# MicroMod-Artemis-ProcessorBoard.net
KiCad netlist of a schematic drawn in EAGLE
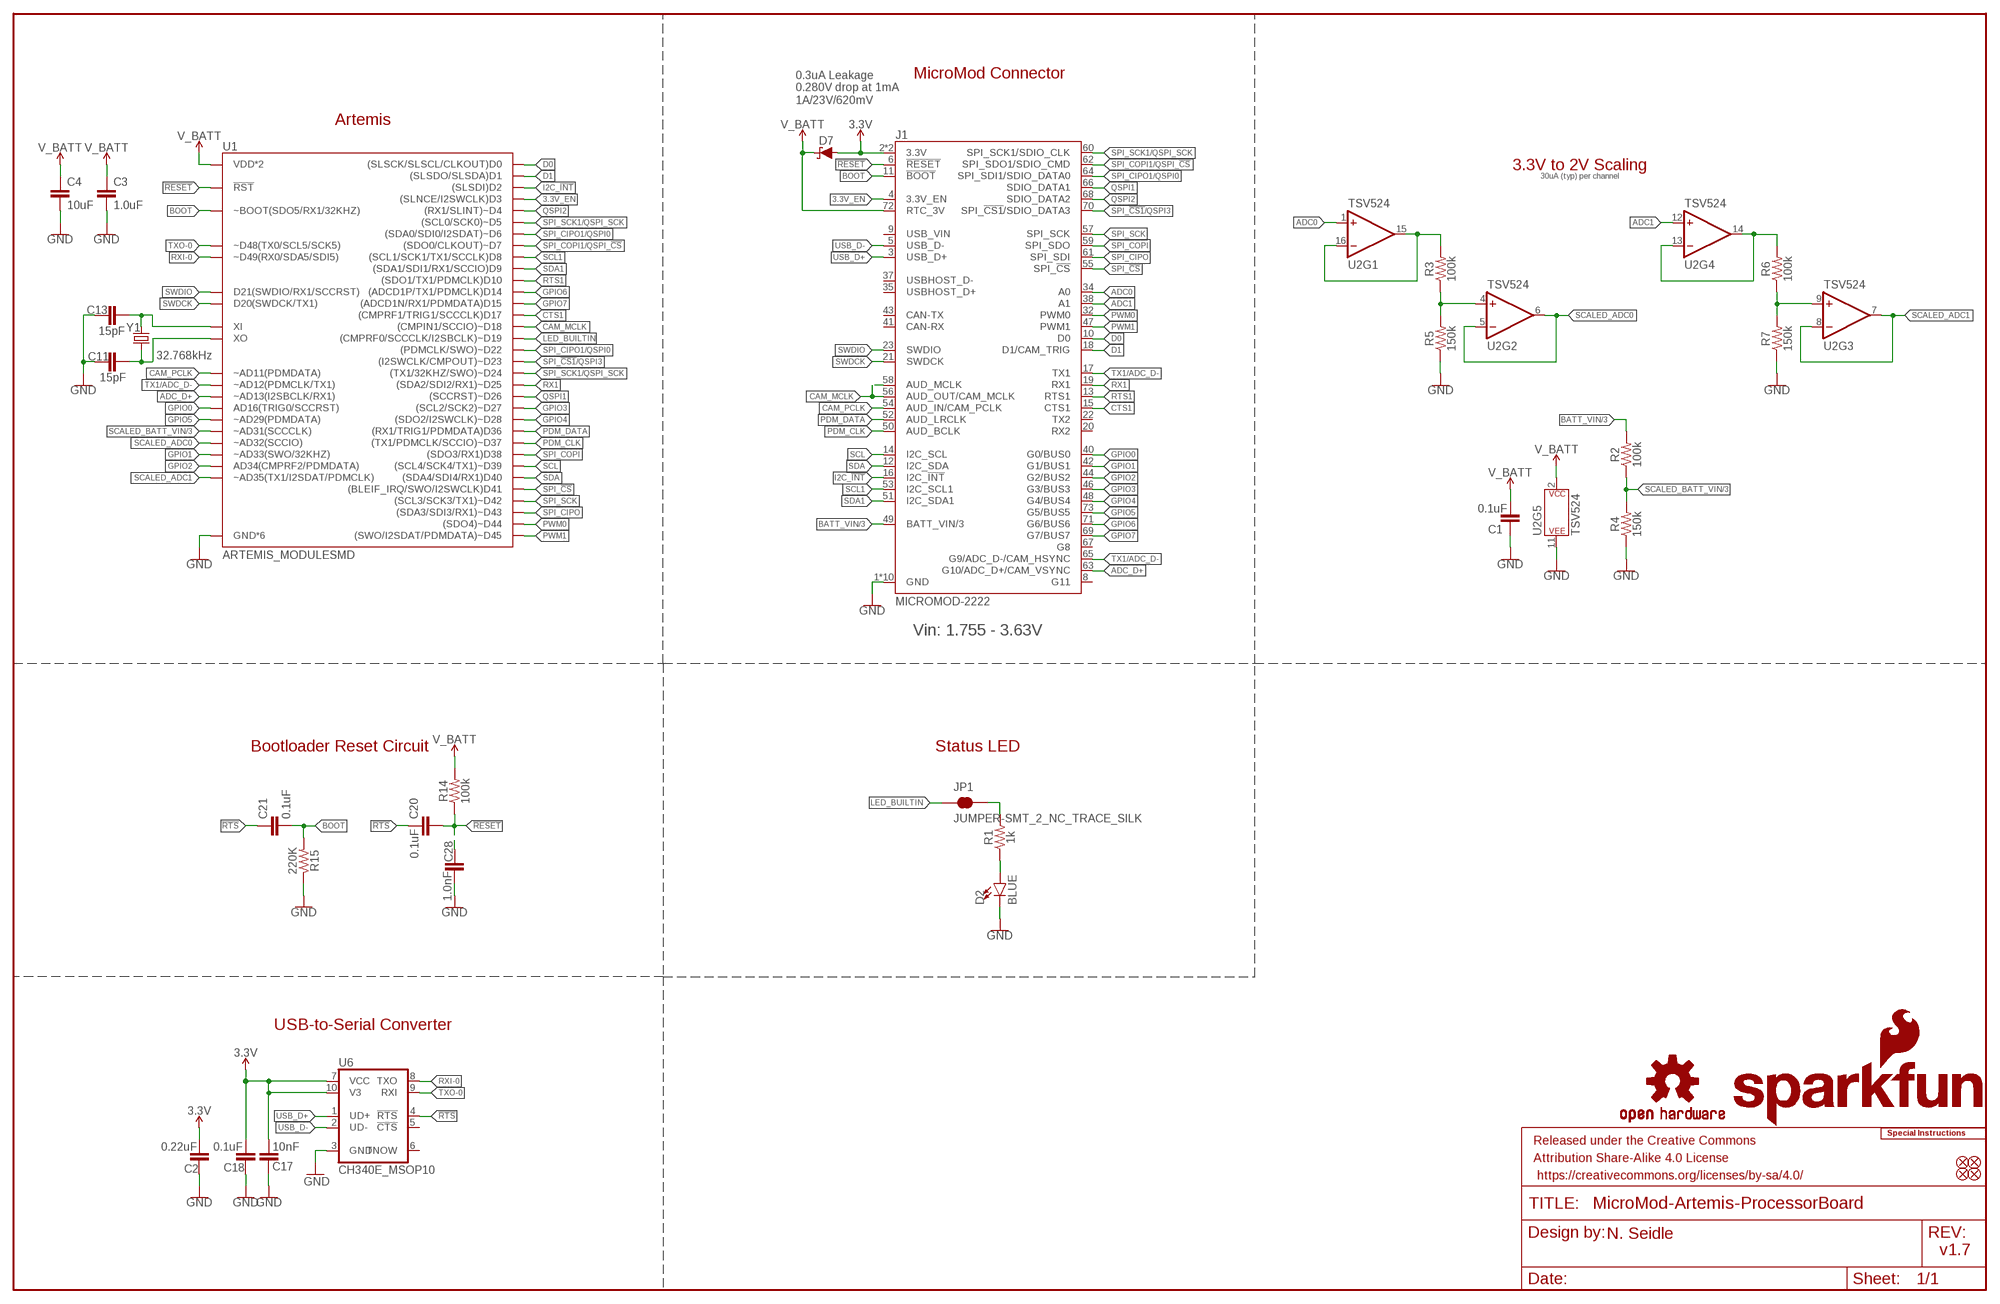
[diagram p0: schematic, sheet 1]

(export (version "E")
  (design (tool "Eeschema 10.0.6"))
  (components
    (comp (ref "C1")
      (value "0.1uF")
      (footprint "eagle-import:0402-TIGHT")
      (libsource (lib "eagle-import") (part "0.1UF-0402T-16V-10%"))
    )
    (comp (ref "C2")
      (value "0.22uF")
      (footprint "eagle-import:0402-TIGHT")
      (libsource (lib "eagle-import") (part "0.22UF-0402T-10V-10%"))
    )
    (comp (ref "C3")
      (value "1.0uF")
      (footprint "eagle-import:0402-TIGHT")
      (libsource (lib "eagle-import") (part "1.0UF-0402T-16V-10%"))
    )
    (comp (ref "C4")
      (value "10uF")
      (footprint "eagle-import:0603")
      (libsource (lib "eagle-import") (part "10UF-0603-6.3V-20%"))
    )
    (comp (ref "C11")
      (value "15pF")
      (footprint "eagle-import:0402-TIGHT")
      (libsource (lib "eagle-import") (part "15PF-0402T-50V-5%"))
    )
    (comp (ref "C13")
      (value "15pF")
      (footprint "eagle-import:0402-TIGHT")
      (libsource (lib "eagle-import") (part "15PF-0402T-50V-5%"))
    )
    (comp (ref "C17")
      (value "10nF")
      (footprint "eagle-import:0402-TIGHT")
      (libsource (lib "eagle-import") (part "10NF-0402T-25V-10%"))
    )
    (comp (ref "C18")
      (value "0.1uF")
      (footprint "eagle-import:0402-TIGHT")
      (libsource (lib "eagle-import") (part "0.1UF-0402T-16V-10%"))
    )
    (comp (ref "C20")
      (value "0.1uF")
      (footprint "eagle-import:0402-TIGHT")
      (libsource (lib "eagle-import") (part "0.1UF-0402T-16V-10%"))
    )
    (comp (ref "C21")
      (value "0.1uF")
      (footprint "eagle-import:0402-TIGHT")
      (libsource (lib "eagle-import") (part "0.1UF-0402T-16V-10%"))
    )
    (comp (ref "C28")
      (value "1.0nF")
      (footprint "eagle-import:0402-TIGHT")
      (libsource (lib "eagle-import") (part "1.0NF/1000PF-0402_TIGHT-50V-10%"))
    )
    (comp (ref "D2")
      (value "BLUE")
      (footprint "eagle-import:LED-0603")
      (libsource (lib "eagle-import") (part "LED-BLUE0603"))
    )
    (comp (ref "D7")
      (value "1A/23V/620mV")
      (footprint "eagle-import:SOD-323")
      (libsource (lib "eagle-import") (part "DIODE-SCHOTTKY-BAT20J"))
    )
    (comp (ref "FD1")
      (value "FIDUCIALUFIDUCIAL")
      (footprint "eagle-import:FIDUCIAL-MICRO")
      (libsource (lib "eagle-import") (part "FIDUCIALUFIDUCIAL"))
    )
    (comp (ref "FD2")
      (value "FIDUCIALUFIDUCIAL")
      (footprint "eagle-import:FIDUCIAL-MICRO")
      (libsource (lib "eagle-import") (part "FIDUCIALUFIDUCIAL"))
    )
    (comp (ref "FD3")
      (value "FIDUCIALUFIDUCIAL")
      (footprint "eagle-import:FIDUCIAL-MICRO")
      (libsource (lib "eagle-import") (part "FIDUCIALUFIDUCIAL"))
    )
    (comp (ref "FD4")
      (value "FIDUCIALUFIDUCIAL")
      (footprint "eagle-import:FIDUCIAL-MICRO")
      (libsource (lib "eagle-import") (part "FIDUCIALUFIDUCIAL"))
    )
    (comp (ref "FRAME1")
      (value "FRAME-LEDGER")
      (footprint "eagle-import:CREATIVE_COMMONS")
      (libsource (lib "eagle-import") (part "FRAME-LEDGER"))
    )
    (comp (ref "J1")
      (value "MICROMOD-2222")
      (footprint "eagle-import:M.2-CARD-E-22")
      (libsource (lib "eagle-import") (part "MICROMOD-2222"))
    )
    (comp (ref "JP1")
      (value "JUMPER-SMT_2_NC_TRACE_SILK")
      (footprint "eagle-import:SMT-JUMPER_2_NC_TRACE_SILK")
      (libsource (lib "eagle-import") (part "JUMPER-SMT_2_NC_TRACE_SILK"))
    )
    (comp (ref "LOGO1")
      (value "SFE_LOGO_NAME_FLAME.1_INCH")
      (footprint "eagle-import:SFE_LOGO_NAME_FLAME_.1")
      (libsource (lib "eagle-import") (part "SFE_LOGO_NAME_FLAME.1_INCH"))
    )
    (comp (ref "LOGO2")
      (value "SFE_LOGO_FLAME.1_INCH")
      (footprint "eagle-import:SFE_LOGO_FLAME_.1")
      (libsource (lib "eagle-import") (part "SFE_LOGO_FLAME.1_INCH"))
    )
    (comp (ref "LOGO3")
      (value "OSHW-LOGOMINI")
      (footprint "eagle-import:OSHW-LOGO-MINI")
      (libsource (lib "eagle-import") (part "OSHW-LOGOMINI"))
    )
    (comp (ref "LOGO4")
      (value "SPECIAL_INSTRUCTIONS-ORDERING")
      (footprint "eagle-import:ORDERING_INSTRUCTIONS")
      (libsource (lib "eagle-import") (part "SPECIAL_INSTRUCTIONS-ORDERING"))
    )
    (comp (ref "R1")
      (value "1k")
      (footprint "eagle-import:0402-TIGHT")
      (libsource (lib "eagle-import") (part "1KOHM-0402T-1/16W-1%"))
    )
    (comp (ref "R2")
      (value "100k")
      (footprint "eagle-import:0402-TIGHT")
      (libsource (lib "eagle-import") (part "100KOHM-0402T-1/16W-1%"))
    )
    (comp (ref "R3")
      (value "100k")
      (footprint "eagle-import:0402-TIGHT")
      (libsource (lib "eagle-import") (part "100KOHM-0402T-1/16W-1%"))
    )
    (comp (ref "R4")
      (value "150k")
      (footprint "eagle-import:0402-TIGHT")
      (libsource (lib "eagle-import") (part "150KOHM-0402T-1/16W-1%"))
    )
    (comp (ref "R5")
      (value "150k")
      (footprint "eagle-import:0402-TIGHT")
      (libsource (lib "eagle-import") (part "150KOHM-0402T-1/16W-1%"))
    )
    (comp (ref "R6")
      (value "100k")
      (footprint "eagle-import:0402-TIGHT")
      (libsource (lib "eagle-import") (part "100KOHM-0402T-1/16W-1%"))
    )
    (comp (ref "R7")
      (value "150k")
      (footprint "eagle-import:0402-TIGHT")
      (libsource (lib "eagle-import") (part "150KOHM-0402T-1/16W-1%"))
    )
    (comp (ref "R14")
      (value "100k")
      (footprint "eagle-import:0402-TIGHT")
      (libsource (lib "eagle-import") (part "100KOHM-0402T-1/16W-1%"))
    )
    (comp (ref "R15")
      (value "220K")
      (footprint "eagle-import:0402-TIGHT")
      (libsource (lib "eagle-import") (part "220KOHM-0402T-1/16W-1%"))
    )
    (comp (ref "U1")
      (value "ARTEMIS_MODULESMD")
      (footprint "eagle-import:ARTEMIS_FP")
      (libsource (lib "eagle-import") (part "ARTEMIS_MODULESMD"))
    )
    (comp (ref "U2")
      (value "TSV524")
      (footprint "eagle-import:QFN-16")
      (libsource (lib "eagle-import") (part "TSV524"))
    )
    (comp (ref "U6")
      (value "CH340E_MSOP10")
      (footprint "eagle-import:MSOP10")
      (libsource (lib "eagle-import") (part "CH340E_MSOP10"))
    )
    (comp (ref "Y1")
      (value "32.768kHz")
      (footprint "eagle-import:CRYSTAL-SMD-3.2X1.5MM")
      (libsource (lib "eagle-import") (part "CRYSTAL-32.768KHZSMD-3.2X1.5"))
    )
  )
  (nets
    (net (code "1") (name "/I2C_~{INT}") (class "Default")
      (node (ref "J1") (pin "16") (pinfunction "I2C_~{INT}_16") (pintype "bidirectional"))
      (node (ref "U1") (pin "D2") (pinfunction "(SLSDI)D2_D2") (pintype "bidirectional"))
    )
    (net (code "2") (name "/SPI_COPI1{slash}QSPI_~{CS}") (class "Default")
      (node (ref "J1") (pin "62") (pinfunction "SPI_SDO1/SDIO_CMD_62") (pintype "bidirectional"))
      (node (ref "U1") (pin "D7") (pinfunction "(SDO0/CLKOUT)~{D7}_D7") (pintype "bidirectional"))
    )
    (net (code "3") (name "/SPI_~{CS1}{slash}QSPI3") (class "Default")
      (node (ref "J1") (pin "70") (pinfunction "SPI_~{CS1}/SDIO_DATA3_70") (pintype "bidirectional"))
      (node (ref "U1") (pin "~D23") (pinfunction "(I2SWCLK/CMPOUT)~{D23}_~D23") (pintype "bidirectional"))
    )
    (net (code "4") (name "/SPI_~{CS}") (class "Default")
      (node (ref "J1") (pin "55") (pinfunction "SPI_~{CS}_55") (pintype "bidirectional"))
      (node (ref "U1") (pin "D41") (pinfunction "(BLEIF_IRQ/SWO/I2SWCLK)D41_D41") (pintype "bidirectional"))
    )
    (net (code "5") (name "/~{RESET}") (class "Default")
      (node (ref "C20") (pin "2") (pinfunction "2_2") (pintype "passive"))
      (node (ref "C28") (pin "1") (pinfunction "1_1") (pintype "passive"))
      (node (ref "J1") (pin "6") (pinfunction "~{RESET}_6") (pintype "bidirectional"))
      (node (ref "R14") (pin "1") (pinfunction "1_1") (pintype "passive"))
      (node (ref "U1") (pin "~RST") (pinfunction "~{RST}_~RST") (pintype "bidirectional"))
    )
    (net (code "6") (name "/~{RTS}") (class "Default")
      (node (ref "C20") (pin "1") (pinfunction "1_1") (pintype "passive"))
      (node (ref "C21") (pin "1") (pinfunction "1_1") (pintype "passive"))
      (node (ref "U6") (pin "4") (pinfunction "~{RTS}_4") (pintype "bidirectional"))
    )
    (net (code "7") (name "3.3V") (class "Default")
      (node (ref "C17") (pin "1") (pinfunction "1_1") (pintype "passive"))
      (node (ref "C18") (pin "1") (pinfunction "1_1") (pintype "passive"))
      (node (ref "C2") (pin "1") (pinfunction "1_1") (pintype "passive"))
      (node (ref "D7") (pin "A") (pinfunction "A_A") (pintype "passive"))
      (node (ref "J1") (pin "2") (pinfunction "3.3V_2") (pintype "bidirectional"))
      (node (ref "J1") (pin "74") (pinfunction "3.3V_74") (pintype "bidirectional"))
      (node (ref "U6") (pin "10") (pinfunction "V3_10") (pintype "bidirectional"))
      (node (ref "U6") (pin "7") (pinfunction "VCC_7") (pintype "bidirectional"))
    )
    (net (code "8") (name "3.3V_EN") (class "Default")
      (node (ref "J1") (pin "4") (pinfunction "3.3V_EN_4") (pintype "bidirectional"))
      (node (ref "U1") (pin "D3") (pinfunction "(SLNCE/I2SWCLK)D3_D3") (pintype "bidirectional"))
    )
    (net (code "9") (name "ADC0") (class "Default")
      (node (ref "J1") (pin "34") (pinfunction "A0_34") (pintype "bidirectional"))
      (node (ref "U2") (pin "1") (pinfunction "+IN_1") (pintype "input"))
    )
    (net (code "10") (name "ADC1") (class "Default")
      (node (ref "J1") (pin "38") (pinfunction "A1_38") (pintype "bidirectional"))
      (node (ref "U2") (pin "12") (pinfunction "+IN_12") (pintype "input"))
    )
    (net (code "11") (name "ADC_D+") (class "Default")
      (node (ref "J1") (pin "63") (pinfunction "G10/ADC_D+/CAM_VSYNC_63") (pintype "bidirectional"))
      (node (ref "U1") (pin "~AD13") (pinfunction "~{AD13(I2SBCLK/RX1})_~AD13") (pintype "bidirectional"))
    )
    (net (code "12") (name "BATT_VIN{slash}3") (class "Default")
      (node (ref "J1") (pin "49") (pinfunction "BATT_VIN/3_49") (pintype "bidirectional"))
      (node (ref "R2") (pin "2") (pinfunction "2_2") (pintype "passive"))
    )
    (net (code "13") (name "BOOT") (class "Default")
      (node (ref "C21") (pin "2") (pinfunction "2_2") (pintype "passive"))
      (node (ref "J1") (pin "11") (pinfunction "~{BOOT}_11") (pintype "bidirectional"))
      (node (ref "R15") (pin "2") (pinfunction "2_2") (pintype "passive"))
      (node (ref "U1") (pin "BOOT") (pinfunction "~{BOOT(SDO5/RX1/32KHZ})_BOOT") (pintype "bidirectional"))
    )
    (net (code "14") (name "CAM_MCLK") (class "Default")
      (node (ref "J1") (pin "56") (pinfunction "AUD_OUT/CAM_MCLK_56") (pintype "bidirectional"))
      (node (ref "J1") (pin "58") (pinfunction "AUD_MCLK_58") (pintype "bidirectional"))
      (node (ref "U1") (pin "~D18") (pinfunction "(CMPIN1/SCCIO)~{D18}_~D18") (pintype "bidirectional"))
    )
    (net (code "15") (name "CAM_PCLK") (class "Default")
      (node (ref "J1") (pin "54") (pinfunction "AUD_IN/CAM_PCLK_54") (pintype "bidirectional"))
      (node (ref "U1") (pin "~AD11") (pinfunction "~{AD11(PDMDATA})_~AD11") (pintype "bidirectional"))
    )
    (net (code "16") (name "CTS1") (class "Default")
      (node (ref "J1") (pin "15") (pinfunction "CTS1_15") (pintype "bidirectional"))
      (node (ref "U1") (pin "D17") (pinfunction "(CMPRF1/TRIG1/SCCCLK)D17_D17") (pintype "bidirectional"))
    )
    (net (code "17") (name "D0") (class "Default")
      (node (ref "J1") (pin "10") (pinfunction "D0_10") (pintype "bidirectional"))
      (node (ref "U1") (pin "D0") (pinfunction "(SLSCK/SLSCL/CLKOUT)D0_D0") (pintype "bidirectional"))
    )
    (net (code "18") (name "D1") (class "Default")
      (node (ref "J1") (pin "18") (pinfunction "D1/CAM_TRIG_18") (pintype "bidirectional"))
      (node (ref "U1") (pin "D1") (pinfunction "(SLSDO/SLSDA)D1_D1") (pintype "bidirectional"))
    )
    (net (code "19") (name "GND") (class "Default")
      (node (ref "C1") (pin "2") (pinfunction "2_2") (pintype "passive"))
      (node (ref "C11") (pin "1") (pinfunction "1_1") (pintype "passive"))
      (node (ref "C13") (pin "1") (pinfunction "1_1") (pintype "passive"))
      (node (ref "C17") (pin "2") (pinfunction "2_2") (pintype "passive"))
      (node (ref "C18") (pin "2") (pinfunction "2_2") (pintype "passive"))
      (node (ref "C2") (pin "2") (pinfunction "2_2") (pintype "passive"))
      (node (ref "C28") (pin "2") (pinfunction "2_2") (pintype "passive"))
      (node (ref "C3") (pin "2") (pinfunction "2_2") (pintype "passive"))
      (node (ref "C4") (pin "2") (pinfunction "2_2") (pintype "passive"))
      (node (ref "D2") (pin "C") (pinfunction "C_C") (pintype "passive"))
      (node (ref "J1") (pin "1") (pinfunction "GND_1") (pintype "bidirectional"))
      (node (ref "J1") (pin "33") (pinfunction "GND_33") (pintype "bidirectional"))
      (node (ref "J1") (pin "36") (pinfunction "GND_36") (pintype "bidirectional"))
      (node (ref "J1") (pin "39") (pinfunction "GND_39") (pintype "bidirectional"))
      (node (ref "J1") (pin "45") (pinfunction "GND_45") (pintype "bidirectional"))
      (node (ref "J1") (pin "7") (pinfunction "GND_7") (pintype "bidirectional"))
      (node (ref "J1") (pin "75") (pinfunction "GND_75") (pintype "bidirectional"))
      (node (ref "J1") (pin "GND1") (pinfunction "GND_GND1") (pintype "bidirectional"))
      (node (ref "J1") (pin "GND2") (pinfunction "GND_GND2") (pintype "bidirectional"))
      (node (ref "J1") (pin "GND3") (pinfunction "GND_GND3") (pintype "bidirectional"))
      (node (ref "R15") (pin "1") (pinfunction "1_1") (pintype "passive"))
      (node (ref "R4") (pin "1") (pinfunction "1_1") (pintype "passive"))
      (node (ref "R5") (pin "1") (pinfunction "1_1") (pintype "passive"))
      (node (ref "R7") (pin "1") (pinfunction "1_1") (pintype "passive"))
      (node (ref "U1") (pin "GND@1") (pinfunction "GND*6_GND@1") (pintype "bidirectional"))
      (node (ref "U1") (pin "GND@22") (pinfunction "GND*6_GND@22") (pintype "bidirectional"))
      (node (ref "U1") (pin "GND@38") (pinfunction "GND*6_GND@38") (pintype "bidirectional"))
      (node (ref "U1") (pin "GND@39") (pinfunction "GND*6_GND@39") (pintype "bidirectional"))
      (node (ref "U1") (pin "GND@47") (pinfunction "GND*6_GND@47") (pintype "bidirectional"))
      (node (ref "U1") (pin "GND@59") (pinfunction "GND*6_GND@59") (pintype "bidirectional"))
      (node (ref "U2") (pin "11") (pinfunction "V-_11") (pintype "bidirectional"))
      (node (ref "U6") (pin "3") (pinfunction "GND_3") (pintype "bidirectional"))
    )
    (net (code "20") (name "GPIO0") (class "Default")
      (node (ref "J1") (pin "40") (pinfunction "G0/BUS0_40") (pintype "bidirectional"))
      (node (ref "U1") (pin "AD16") (pinfunction "AD16(TRIG0/SCCRST)_AD16") (pintype "bidirectional"))
    )
    (net (code "21") (name "GPIO1") (class "Default")
      (node (ref "J1") (pin "42") (pinfunction "G1/BUS1_42") (pintype "bidirectional"))
      (node (ref "U1") (pin "~AD33/SWO") (pinfunction "~{AD33(SWO/32KHZ})_~AD33/SWO") (pintype "bidirectional"))
    )
    (net (code "22") (name "GPIO2") (class "Default")
      (node (ref "J1") (pin "44") (pinfunction "G2/BUS2_44") (pintype "bidirectional"))
      (node (ref "U1") (pin "AD34") (pinfunction "AD34(CMPRF2/PDMDATA)_AD34") (pintype "bidirectional"))
    )
    (net (code "23") (name "GPIO3") (class "Default")
      (node (ref "J1") (pin "46") (pinfunction "G3/BUS3_46") (pintype "bidirectional"))
      (node (ref "U1") (pin "~D27") (pinfunction "(SCL2/SCK2)~{D27}_~D27") (pintype "bidirectional"))
    )
    (net (code "24") (name "GPIO4") (class "Default")
      (node (ref "J1") (pin "48") (pinfunction "G4/BUS4_48") (pintype "bidirectional"))
      (node (ref "U1") (pin "~D28") (pinfunction "(SDO2/I2SWCLK)~{D28}_~D28") (pintype "bidirectional"))
    )
    (net (code "25") (name "GPIO5") (class "Default")
      (node (ref "J1") (pin "73") (pinfunction "G5/BUS5_73") (pintype "bidirectional"))
      (node (ref "U1") (pin "~AD29") (pinfunction "~{AD29(PDMDATA})_~AD29") (pintype "bidirectional"))
    )
    (net (code "26") (name "GPIO6") (class "Default")
      (node (ref "J1") (pin "71") (pinfunction "G6/BUS6_71") (pintype "bidirectional"))
      (node (ref "U1") (pin "D14") (pinfunction "(ADCD1P/TX1/PDMCLK)D14_D14") (pintype "bidirectional"))
    )
    (net (code "27") (name "GPIO7") (class "Default")
      (node (ref "J1") (pin "69") (pinfunction "G7/BUS7_69") (pintype "bidirectional"))
      (node (ref "U1") (pin "D15") (pinfunction "(ADCD1N/RX1/PDMDATA)D15_D15") (pintype "bidirectional"))
    )
    (net (code "28") (name "LED_BUILTIN") (class "Default")
      (node (ref "JP1") (pin "1") (pinfunction "1_1") (pintype "passive"))
      (node (ref "U1") (pin "~D19") (pinfunction "(CMPRF0/SCCCLK/I2SBCLK)~{D19}_~D19") (pintype "bidirectional"))
    )
    (net (code "29") (name "Net-(D2-PadA)") (class "Default")
      (node (ref "D2") (pin "A") (pinfunction "A_A") (pintype "passive"))
      (node (ref "R1") (pin "1") (pinfunction "1_1") (pintype "passive"))
    )
    (net (code "30") (name "Net-(JP1-Pad2)") (class "Default")
      (node (ref "JP1") (pin "2") (pinfunction "2_2") (pintype "passive"))
      (node (ref "R1") (pin "2") (pinfunction "2_2") (pintype "passive"))
    )
    (net (code "31") (name "Net-(U2A--IN)") (class "Default")
      (node (ref "R3") (pin "2") (pinfunction "2_2") (pintype "passive"))
      (node (ref "U2") (pin "15") (pinfunction "OUT_15") (pintype "output"))
      (node (ref "U2") (pin "16") (pinfunction "-IN_16") (pintype "input"))
    )
    (net (code "32") (name "Net-(U2B-+IN)") (class "Default")
      (node (ref "R3") (pin "1") (pinfunction "1_1") (pintype "passive"))
      (node (ref "R5") (pin "2") (pinfunction "2_2") (pintype "passive"))
      (node (ref "U2") (pin "4") (pinfunction "+IN_4") (pintype "input"))
    )
    (net (code "33") (name "Net-(U2C-+IN)") (class "Default")
      (node (ref "R6") (pin "1") (pinfunction "1_1") (pintype "passive"))
      (node (ref "R7") (pin "2") (pinfunction "2_2") (pintype "passive"))
      (node (ref "U2") (pin "9") (pinfunction "+IN_9") (pintype "input"))
    )
    (net (code "34") (name "Net-(U2D--IN)") (class "Default")
      (node (ref "R6") (pin "2") (pinfunction "2_2") (pintype "passive"))
      (node (ref "U2") (pin "13") (pinfunction "-IN_13") (pintype "input"))
      (node (ref "U2") (pin "14") (pinfunction "OUT_14") (pintype "output"))
    )
    (net (code "35") (name "Net-(Y1-1)") (class "Default")
      (node (ref "C13") (pin "2") (pinfunction "2_2") (pintype "passive"))
      (node (ref "U1") (pin "XI") (pinfunction "XI_XI") (pintype "bidirectional"))
      (node (ref "Y1") (pin "P$1") (pinfunction "1_P$1") (pintype "passive"))
    )
    (net (code "36") (name "Net-(Y1-2)") (class "Default")
      (node (ref "C11") (pin "2") (pinfunction "2_2") (pintype "passive"))
      (node (ref "U1") (pin "XO") (pinfunction "XO_XO") (pintype "bidirectional"))
      (node (ref "Y1") (pin "P$2") (pinfunction "2_P$2") (pintype "passive"))
    )
    (net (code "37") (name "PDM_CLK") (class "Default")
      (node (ref "J1") (pin "50") (pinfunction "AUD_BCLK_50") (pintype "bidirectional"))
      (node (ref "U1") (pin "~D37") (pinfunction "(TX1/PDMCLK/SCCIO)~{D37}_~D37") (pintype "bidirectional"))
    )
    (net (code "38") (name "PDM_DATA") (class "Default")
      (node (ref "J1") (pin "52") (pinfunction "AUD_LRCLK_52") (pintype "bidirectional"))
      (node (ref "U1") (pin "D36") (pinfunction "(RX1/TRIG1/PDMDATA)D36_D36") (pintype "bidirectional"))
    )
    (net (code "39") (name "PWM0") (class "Default")
      (node (ref "J1") (pin "32") (pinfunction "PWM0_32") (pintype "bidirectional"))
      (node (ref "U1") (pin "~D44") (pinfunction "(SDO4)~{D44}_~D44") (pintype "bidirectional"))
    )
    (net (code "40") (name "PWM1") (class "Default")
      (node (ref "J1") (pin "47") (pinfunction "PWM1_47") (pintype "bidirectional"))
      (node (ref "U1") (pin "~D45") (pinfunction "(SWO/I2SDAT/PDMDATA)~{D45}_~D45") (pintype "bidirectional"))
    )
    (net (code "41") (name "QSPI1") (class "Default")
      (node (ref "J1") (pin "66") (pinfunction "SDIO_DATA1_66") (pintype "bidirectional"))
      (node (ref "U1") (pin "~D26") (pinfunction "(SCCRST)~{D26}_~D26") (pintype "bidirectional"))
    )
    (net (code "42") (name "QSPI2") (class "Default")
      (node (ref "J1") (pin "68") (pinfunction "SDIO_DATA2_68") (pintype "bidirectional"))
      (node (ref "U1") (pin "~D4") (pinfunction "(RX1/SLINT)~{D4}_~D4") (pintype "bidirectional"))
    )
    (net (code "43") (name "RTS1") (class "Default")
      (node (ref "J1") (pin "13") (pinfunction "RTS1_13") (pintype "bidirectional"))
      (node (ref "U1") (pin "D10") (pinfunction "(SDO1/TX1/PDMCLK)D10_D10") (pintype "bidirectional"))
    )
    (net (code "44") (name "RX1") (class "Default")
      (node (ref "J1") (pin "19") (pinfunction "RX1_19") (pintype "bidirectional"))
      (node (ref "U1") (pin "~D25") (pinfunction "(SDA2/SDI2/RX1)~{D25}_~D25") (pintype "bidirectional"))
    )
    (net (code "45") (name "RXI-0") (class "Default")
      (node (ref "U1") (pin "RXI-0") (pinfunction "~{D49(RX0/SDA5/SDI5})_RXI-0") (pintype "bidirectional"))
      (node (ref "U6") (pin "8") (pinfunction "TXO_8") (pintype "bidirectional"))
    )
    (net (code "46") (name "SCALED_ADC0") (class "Default")
      (node (ref "U1") (pin "~AD32") (pinfunction "~{AD32(SCCIO})_~AD32") (pintype "bidirectional"))
      (node (ref "U2") (pin "5") (pinfunction "-IN_5") (pintype "input"))
      (node (ref "U2") (pin "6") (pinfunction "OUT_6") (pintype "output"))
    )
    (net (code "47") (name "SCALED_ADC1") (class "Default")
      (node (ref "U1") (pin "~AD35") (pinfunction "~{AD35(TX1/I2SDAT/PDMCLK})_~AD35") (pintype "bidirectional"))
      (node (ref "U2") (pin "7") (pinfunction "OUT_7") (pintype "output"))
      (node (ref "U2") (pin "8") (pinfunction "-IN_8") (pintype "input"))
    )
    (net (code "48") (name "SCALED_BATT_VIN{slash}3") (class "Default")
      (node (ref "R2") (pin "1") (pinfunction "1_1") (pintype "passive"))
      (node (ref "R4") (pin "2") (pinfunction "2_2") (pintype "passive"))
      (node (ref "U1") (pin "~AD31") (pinfunction "~{AD31(SCCCLK})_~AD31") (pintype "bidirectional"))
    )
    (net (code "49") (name "SCL") (class "Default")
      (node (ref "J1") (pin "14") (pinfunction "I2C_SCL_14") (pintype "bidirectional"))
      (node (ref "U1") (pin "~D39") (pinfunction "(SCL4/SCK4/TX1)~{D39}_~D39") (pintype "bidirectional"))
    )
    (net (code "50") (name "SCL1") (class "Default")
      (node (ref "J1") (pin "53") (pinfunction "I2C_SCL1_53") (pintype "bidirectional"))
      (node (ref "U1") (pin "D8") (pinfunction "(SCL1/SCK1/TX1/SCCLK)D8_D8") (pintype "bidirectional"))
    )
    (net (code "51") (name "SDA") (class "Default")
      (node (ref "J1") (pin "12") (pinfunction "I2C_SDA_12") (pintype "bidirectional"))
      (node (ref "U1") (pin "D40") (pinfunction "(SDA4/SDI4/RX1)D40_D40") (pintype "bidirectional"))
    )
    (net (code "52") (name "SDA1") (class "Default")
      (node (ref "J1") (pin "51") (pinfunction "I2C_SDA1_51") (pintype "bidirectional"))
      (node (ref "U1") (pin "D9") (pinfunction "(SDA1/SDI1/RX1/SCCIO)D9_D9") (pintype "bidirectional"))
    )
    (net (code "53") (name "SPI_CIPO") (class "Default")
      (node (ref "J1") (pin "61") (pinfunction "SPI_SDI_61") (pintype "bidirectional"))
      (node (ref "U1") (pin "~D43") (pinfunction "(SDA3/SDI3/RX1)~{D43}_~D43") (pintype "bidirectional"))
    )
    (net (code "54") (name "SPI_CIPO1{slash}QSPI0") (class "Default")
      (node (ref "J1") (pin "64") (pinfunction "SPI_SDI1/SDIO_DATA0_64") (pintype "bidirectional"))
      (node (ref "U1") (pin "~D22") (pinfunction "(PDMCLK/SWO)~{D22}_~D22") (pintype "bidirectional"))
      (node (ref "U1") (pin "~D6") (pinfunction "(SDA0/SDI0/I2SDAT)~{D6}_~D6") (pintype "bidirectional"))
    )
    (net (code "55") (name "SPI_COPI") (class "Default")
      (node (ref "J1") (pin "59") (pinfunction "SPI_SDO_59") (pintype "bidirectional"))
      (node (ref "U1") (pin "D38") (pinfunction "(SDO3/RX1)D38_D38") (pintype "bidirectional"))
    )
    (net (code "56") (name "SPI_SCK") (class "Default")
      (node (ref "J1") (pin "57") (pinfunction "SPI_SCK_57") (pintype "bidirectional"))
      (node (ref "U1") (pin "~D42") (pinfunction "(SCL3/SCK3/TX1)~{D42}_~D42") (pintype "bidirectional"))
    )
    (net (code "57") (name "SPI_SCK1{slash}QSPI_SCK") (class "Default")
      (node (ref "J1") (pin "60") (pinfunction "SPI_SCK1/SDIO_CLK_60") (pintype "bidirectional"))
      (node (ref "U1") (pin "~D24") (pinfunction "(TX1/32KHZ/SWO)~{D24}_~D24") (pintype "bidirectional"))
      (node (ref "U1") (pin "~D5") (pinfunction "(SCL0/SCK0)~{D5}_~D5") (pintype "bidirectional"))
    )
    (net (code "58") (name "SWDCK") (class "Default")
      (node (ref "J1") (pin "21") (pinfunction "SWDCK_21") (pintype "bidirectional"))
      (node (ref "U1") (pin "SWDCK") (pinfunction "D20(SWDCK/TX1)_SWDCK") (pintype "bidirectional"))
    )
    (net (code "59") (name "SWDIO") (class "Default")
      (node (ref "J1") (pin "23") (pinfunction "SWDIO_23") (pintype "bidirectional"))
      (node (ref "U1") (pin "SWDIO") (pinfunction "D21(SWDIO/RX1/SCCRST)_SWDIO") (pintype "bidirectional"))
    )
    (net (code "60") (name "TX1{slash}ADC_D-") (class "Default")
      (node (ref "J1") (pin "17") (pinfunction "TX1_17") (pintype "bidirectional"))
      (node (ref "J1") (pin "65") (pinfunction "G9/ADC_D-/CAM_HSYNC_65") (pintype "bidirectional"))
      (node (ref "U1") (pin "~AD12") (pinfunction "~{AD12(PDMCLK/TX1})_~AD12") (pintype "bidirectional"))
    )
    (net (code "61") (name "TXO-0") (class "Default")
      (node (ref "U1") (pin "TXO-0") (pinfunction "~{D48(TX0/SCL5/SCK5})_TXO-0") (pintype "bidirectional"))
      (node (ref "U6") (pin "9") (pinfunction "RXI_9") (pintype "bidirectional"))
    )
    (net (code "62") (name "USB_D+") (class "Default")
      (node (ref "J1") (pin "3") (pinfunction "USB_D+_3") (pintype "bidirectional"))
      (node (ref "U6") (pin "1") (pinfunction "UD+_1") (pintype "bidirectional"))
    )
    (net (code "63") (name "USB_D-") (class "Default")
      (node (ref "J1") (pin "5") (pinfunction "USB_D-_5") (pintype "bidirectional"))
      (node (ref "U6") (pin "2") (pinfunction "UD-_2") (pintype "bidirectional"))
    )
    (net (code "64") (name "V_BATT") (class "Default")
      (node (ref "C1") (pin "1") (pinfunction "1_1") (pintype "passive"))
      (node (ref "C3") (pin "1") (pinfunction "1_1") (pintype "passive"))
      (node (ref "C4") (pin "1") (pinfunction "1_1") (pintype "passive"))
      (node (ref "D7") (pin "C") (pinfunction "C_C") (pintype "passive"))
      (node (ref "J1") (pin "72") (pinfunction "RTC_3V_72") (pintype "bidirectional"))
      (node (ref "R14") (pin "2") (pinfunction "2_2") (pintype "passive"))
      (node (ref "U1") (pin "VDD@36") (pinfunction "VDD*2_VDD@36") (pintype "bidirectional"))
      (node (ref "U1") (pin "VDD@37") (pinfunction "VDD*2_VDD@37") (pintype "bidirectional"))
      (node (ref "U2") (pin "2") (pinfunction "V+_2") (pintype "bidirectional"))
    )
    (net (code "65") (name "unconnected-(J1-CAN-RX-Pad41)") (class "Default")
      (node (ref "J1") (pin "41") (pinfunction "CAN-RX_41") (pintype "bidirectional"))
    )
    (net (code "66") (name "unconnected-(J1-CAN-TX-Pad43)") (class "Default")
      (node (ref "J1") (pin "43") (pinfunction "CAN-TX_43") (pintype "bidirectional"))
    )
    (net (code "67") (name "unconnected-(J1-G8-Pad67)") (class "Default")
      (node (ref "J1") (pin "67") (pinfunction "G8_67") (pintype "bidirectional"))
    )
    (net (code "68") (name "unconnected-(J1-G11-Pad8)") (class "Default")
      (node (ref "J1") (pin "8") (pinfunction "G11_8") (pintype "bidirectional"))
    )
    (net (code "69") (name "unconnected-(J1-RX2-Pad20)") (class "Default")
      (node (ref "J1") (pin "20") (pinfunction "RX2_20") (pintype "bidirectional"))
    )
    (net (code "70") (name "unconnected-(J1-TX2-Pad22)") (class "Default")
      (node (ref "J1") (pin "22") (pinfunction "TX2_22") (pintype "bidirectional"))
    )
    (net (code "71") (name "unconnected-(J1-USBHOST_D+-Pad35)") (class "Default")
      (node (ref "J1") (pin "35") (pinfunction "USBHOST_D+_35") (pintype "bidirectional"))
    )
    (net (code "72") (name "unconnected-(J1-USBHOST_D--Pad37)") (class "Default")
      (node (ref "J1") (pin "37") (pinfunction "USBHOST_D-_37") (pintype "bidirectional"))
    )
    (net (code "73") (name "unconnected-(J1-USB_VIN-Pad9)") (class "Default")
      (node (ref "J1") (pin "9") (pinfunction "USB_VIN_9") (pintype "bidirectional"))
    )
    (net (code "74") (name "unconnected-(U6-TNOW-Pad6)") (class "Default")
      (node (ref "U6") (pin "6") (pinfunction "TNOW_6") (pintype "bidirectional"))
    )
    (net (code "75") (name "unconnected-(U6-~{CTS}-Pad5)") (class "Default")
      (node (ref "U6") (pin "5") (pinfunction "~{CTS}_5") (pintype "bidirectional"))
    )
  )
)
